# uCschematic.net
KiCad netlist of a schematic drawn in EAGLE
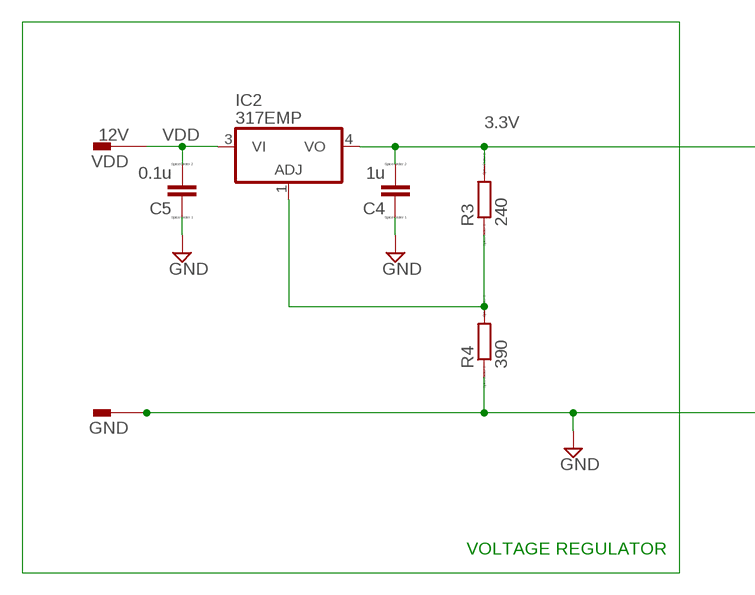
[diagram p0: schematic, sheet 1, part 1 of 2]
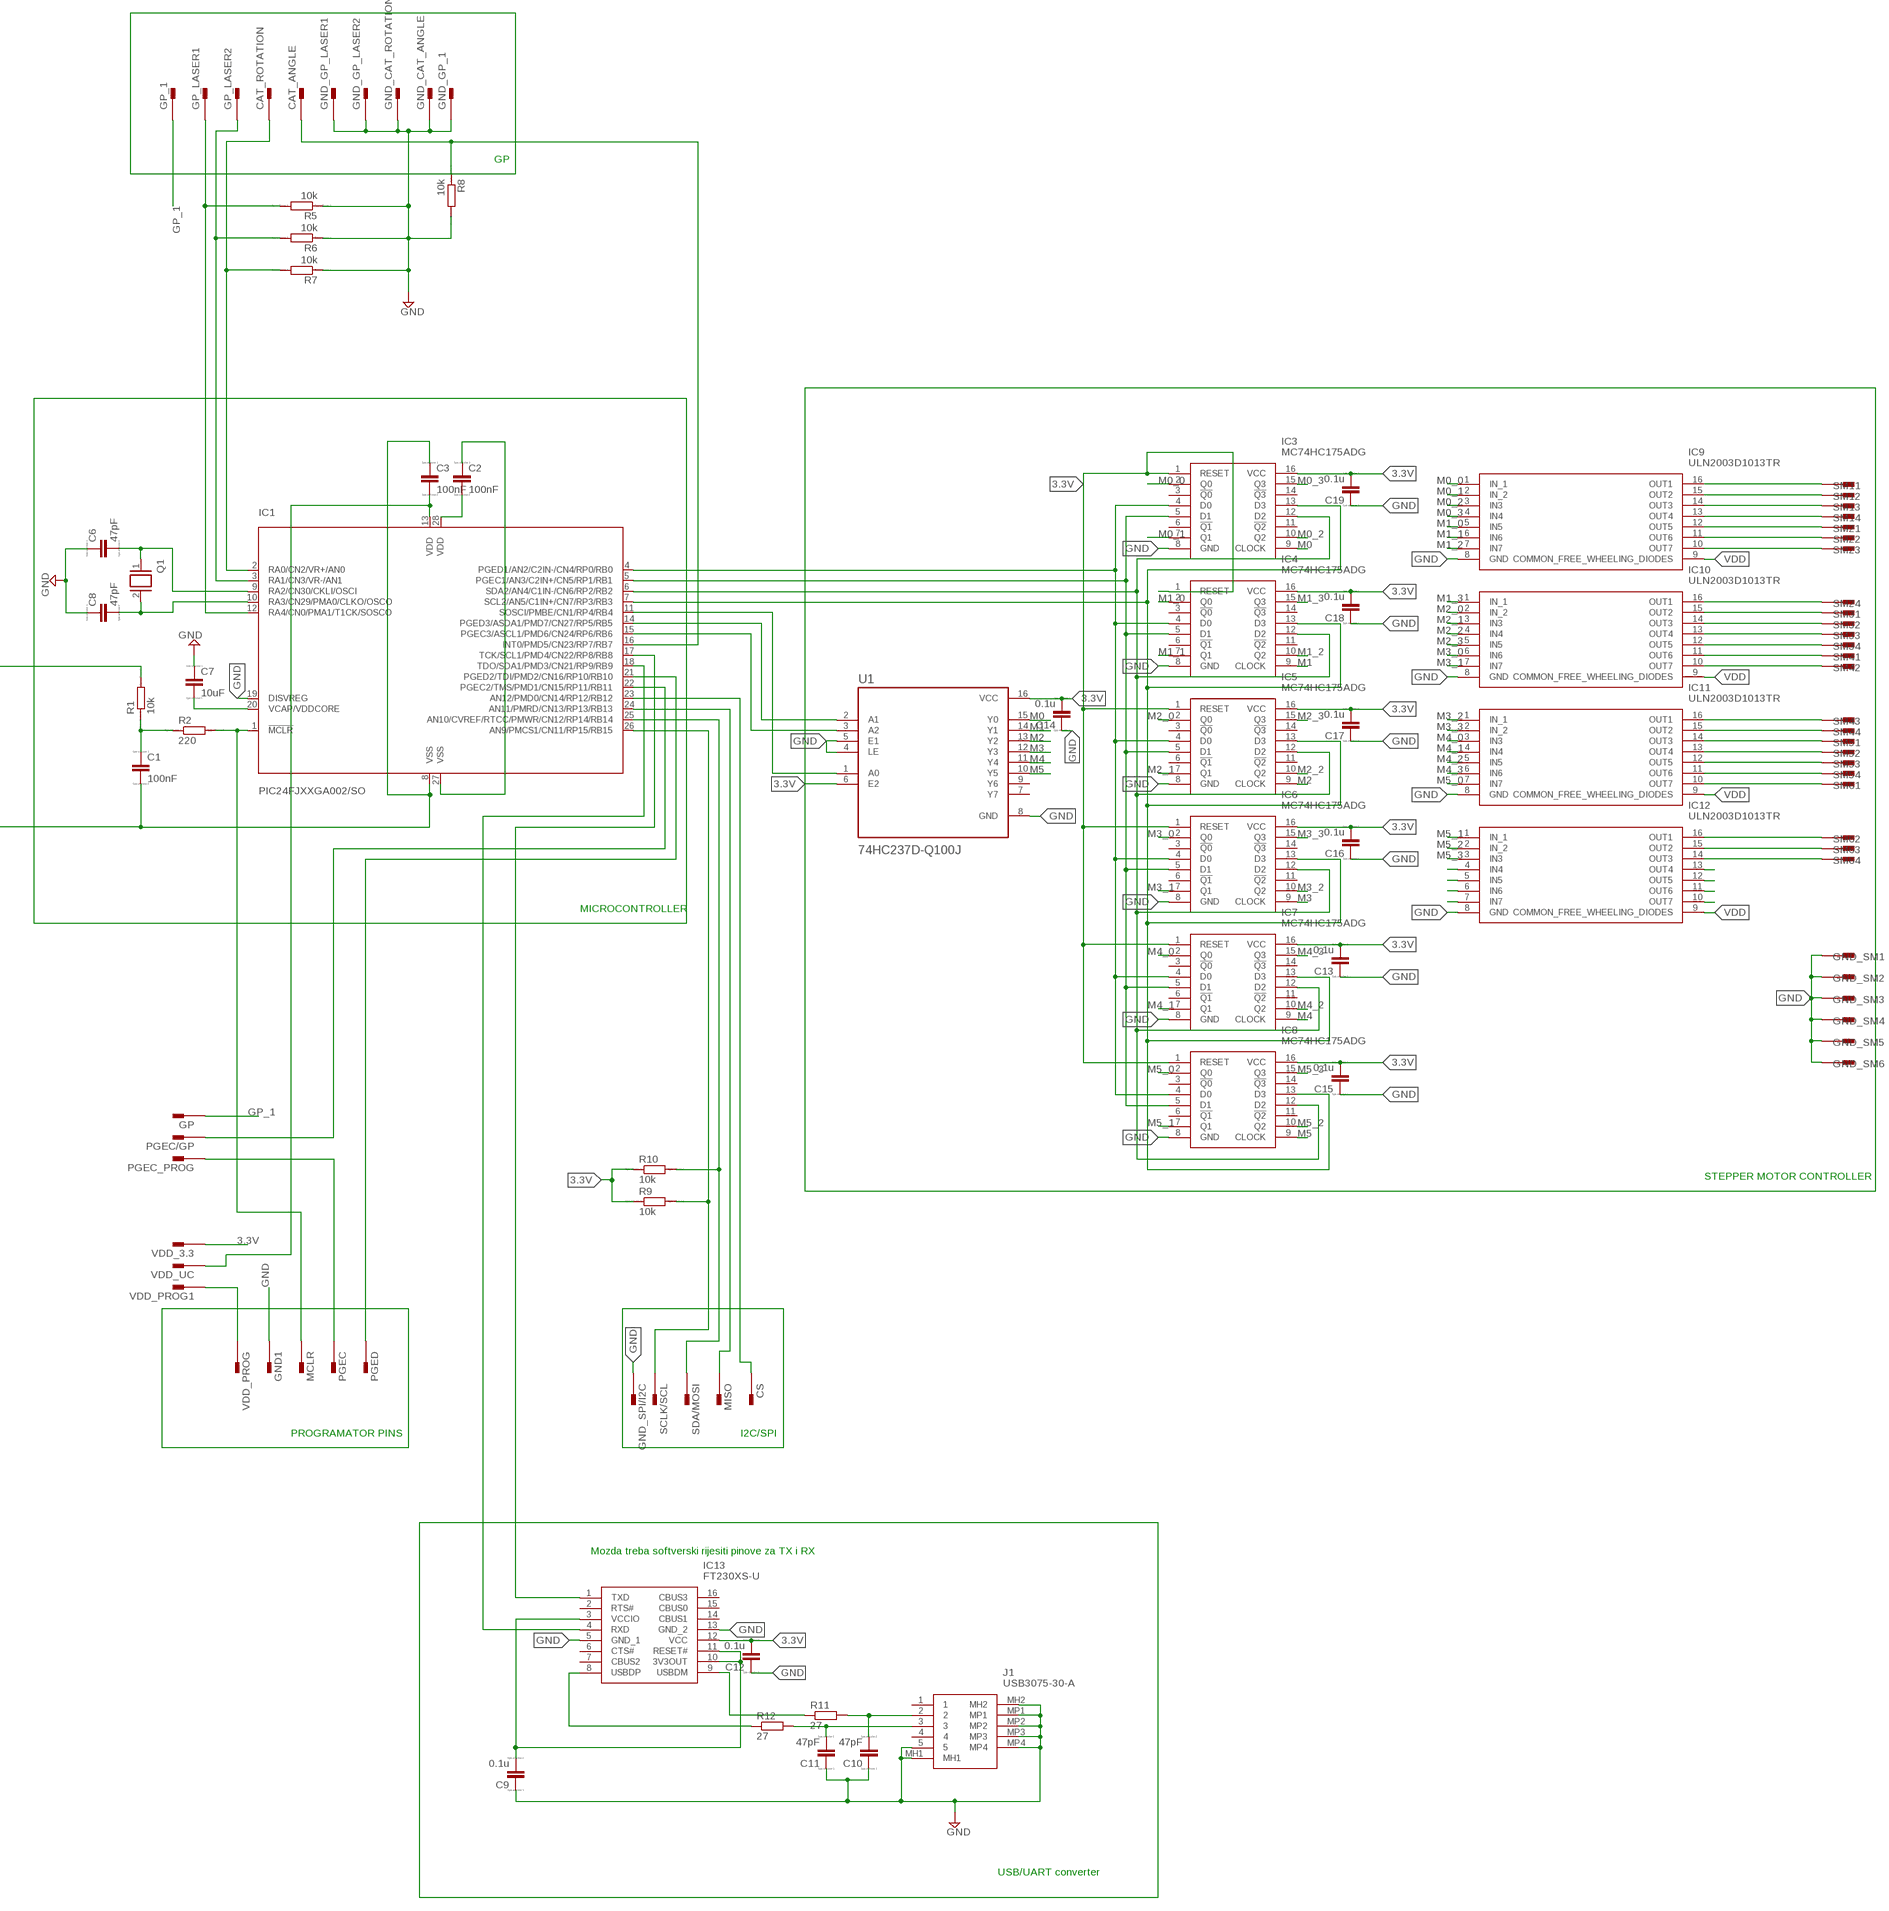
[diagram p1: schematic, sheet 1, part 2 of 2]

(export (version "E")
  (design (tool "Eeschema 10.0.6"))
  (components
    (comp (ref "C1")
      (value "100nF")
      (footprint "eagle-import:C0805")
      (libsource (lib "eagle-import") (part "C"))
    )
    (comp (ref "C2")
      (value "100nF")
      (footprint "eagle-import:C0805")
      (libsource (lib "eagle-import") (part "C"))
    )
    (comp (ref "C3")
      (value "100nF")
      (footprint "eagle-import:C0805")
      (libsource (lib "eagle-import") (part "C"))
    )
    (comp (ref "C4")
      (value "1u")
      (footprint "eagle-import:C0805")
      (libsource (lib "eagle-import") (part "C"))
    )
    (comp (ref "C5")
      (value "0.1u")
      (footprint "eagle-import:C0805")
      (libsource (lib "eagle-import") (part "C"))
    )
    (comp (ref "C6")
      (value "47pF")
      (footprint "eagle-import:C0805")
      (libsource (lib "eagle-import") (part "C"))
    )
    (comp (ref "C7")
      (value "10uF")
      (footprint "eagle-import:C0805")
      (libsource (lib "eagle-import") (part "C"))
    )
    (comp (ref "C8")
      (value "47pF")
      (footprint "eagle-import:C0805")
      (libsource (lib "eagle-import") (part "C"))
    )
    (comp (ref "C9")
      (value "0.1u")
      (footprint "eagle-import:C0805")
      (libsource (lib "eagle-import") (part "C"))
    )
    (comp (ref "C10")
      (value "47pF")
      (footprint "eagle-import:C0805")
      (libsource (lib "eagle-import") (part "C"))
    )
    (comp (ref "C11")
      (value "47pF")
      (footprint "eagle-import:C0805")
      (libsource (lib "eagle-import") (part "C"))
    )
    (comp (ref "C12")
      (value "0.1u")
      (footprint "eagle-import:C0805")
      (libsource (lib "eagle-import") (part "C"))
    )
    (comp (ref "C13")
      (value "0.1u")
      (footprint "eagle-import:C0805")
      (libsource (lib "eagle-import") (part "C"))
    )
    (comp (ref "C14")
      (value "0.1u")
      (footprint "eagle-import:C0805")
      (libsource (lib "eagle-import") (part "C"))
    )
    (comp (ref "C15")
      (value "0.1u")
      (footprint "eagle-import:C0805")
      (libsource (lib "eagle-import") (part "C"))
    )
    (comp (ref "C16")
      (value "0.1u")
      (footprint "eagle-import:C0805")
      (libsource (lib "eagle-import") (part "C"))
    )
    (comp (ref "C17")
      (value "0.1u")
      (footprint "eagle-import:C0805")
      (libsource (lib "eagle-import") (part "C"))
    )
    (comp (ref "C18")
      (value "0.1u")
      (footprint "eagle-import:C0805")
      (libsource (lib "eagle-import") (part "C"))
    )
    (comp (ref "C19")
      (value "0.1u")
      (footprint "eagle-import:C0805")
      (libsource (lib "eagle-import") (part "C"))
    )
    (comp (ref "CAT_ANGLE")
      (value "PIN1-2")
      (footprint "eagle-import:62221")
      (fields (field (name "MF") "TYCO ELECTRONICS") (field (name "MPN") "62221-1"))
      (libsource (lib "eagle-import") (part "PIN1-2"))
    )
    (comp (ref "CAT_ROTATION")
      (value "PIN1-2")
      (footprint "eagle-import:62221")
      (fields (field (name "MF") "TYCO ELECTRONICS") (field (name "MPN") "62221-1"))
      (libsource (lib "eagle-import") (part "PIN1-2"))
    )
    (comp (ref "CS")
      (value "PIN1-2")
      (footprint "eagle-import:62221")
      (fields (field (name "MF") "TYCO ELECTRONICS") (field (name "MPN") "62221-1"))
      (libsource (lib "eagle-import") (part "PIN1-2"))
    )
    (comp (ref "GND")
      (value "PIN1-2")
      (footprint "eagle-import:62221")
      (fields (field (name "MF") "TYCO ELECTRONICS") (field (name "MPN") "62221-1"))
      (libsource (lib "eagle-import") (part "PIN1-2"))
    )
    (comp (ref "GND1")
      (value "PIN1-2")
      (footprint "eagle-import:62221")
      (fields (field (name "MF") "TYCO ELECTRONICS") (field (name "MPN") "62221-1"))
      (libsource (lib "eagle-import") (part "PIN1-2"))
    )
    (comp (ref "GND_CAT_ANGLE")
      (value "PIN1-2")
      (footprint "eagle-import:62221")
      (fields (field (name "MF") "TYCO ELECTRONICS") (field (name "MPN") "62221-1"))
      (libsource (lib "eagle-import") (part "PIN1-2"))
    )
    (comp (ref "GND_CAT_ROTATION")
      (value "PIN1-2")
      (footprint "eagle-import:62221")
      (fields (field (name "MF") "TYCO ELECTRONICS") (field (name "MPN") "62221-1"))
      (libsource (lib "eagle-import") (part "PIN1-2"))
    )
    (comp (ref "GND_GP_1")
      (value "PIN1-2")
      (footprint "eagle-import:62221")
      (fields (field (name "MF") "TYCO ELECTRONICS") (field (name "MPN") "62221-1"))
      (libsource (lib "eagle-import") (part "PIN1-2"))
    )
    (comp (ref "GND_GP_LASER1")
      (value "PIN1-2")
      (footprint "eagle-import:62221")
      (fields (field (name "MF") "TYCO ELECTRONICS") (field (name "MPN") "62221-1"))
      (libsource (lib "eagle-import") (part "PIN1-2"))
    )
    (comp (ref "GND_GP_LASER2")
      (value "PIN1-2")
      (footprint "eagle-import:62221")
      (fields (field (name "MF") "TYCO ELECTRONICS") (field (name "MPN") "62221-1"))
      (libsource (lib "eagle-import") (part "PIN1-2"))
    )
    (comp (ref "GND_SM1")
      (value "PIN1-2")
      (footprint "eagle-import:62221")
      (fields (field (name "MF") "TYCO ELECTRONICS") (field (name "MPN") "62221-1"))
      (libsource (lib "eagle-import") (part "PIN1-2"))
    )
    (comp (ref "GND_SM2")
      (value "PIN1-2")
      (footprint "eagle-import:62221")
      (fields (field (name "MF") "TYCO ELECTRONICS") (field (name "MPN") "62221-1"))
      (libsource (lib "eagle-import") (part "PIN1-2"))
    )
    (comp (ref "GND_SM3")
      (value "PIN1-2")
      (footprint "eagle-import:62221")
      (fields (field (name "MF") "TYCO ELECTRONICS") (field (name "MPN") "62221-1"))
      (libsource (lib "eagle-import") (part "PIN1-2"))
    )
    (comp (ref "GND_SM4")
      (value "PIN1-2")
      (footprint "eagle-import:62221")
      (fields (field (name "MF") "TYCO ELECTRONICS") (field (name "MPN") "62221-1"))
      (libsource (lib "eagle-import") (part "PIN1-2"))
    )
    (comp (ref "GND_SM5")
      (value "PIN1-2")
      (footprint "eagle-import:62221")
      (fields (field (name "MF") "TYCO ELECTRONICS") (field (name "MPN") "62221-1"))
      (libsource (lib "eagle-import") (part "PIN1-2"))
    )
    (comp (ref "GND_SM6")
      (value "PIN1-2")
      (footprint "eagle-import:62221")
      (fields (field (name "MF") "TYCO ELECTRONICS") (field (name "MPN") "62221-1"))
      (libsource (lib "eagle-import") (part "PIN1-2"))
    )
    (comp (ref "GND_SPI/I2C")
      (value "PIN1-2")
      (footprint "eagle-import:62221")
      (fields (field (name "MF") "TYCO ELECTRONICS") (field (name "MPN") "62221-1"))
      (libsource (lib "eagle-import") (part "PIN1-2"))
    )
    (comp (ref "GP")
      (value "PIN1-2")
      (footprint "eagle-import:62221")
      (fields (field (name "MF") "TYCO ELECTRONICS") (field (name "MPN") "62221-1"))
      (libsource (lib "eagle-import") (part "PIN1-2"))
    )
    (comp (ref "GP_1")
      (value "PIN1-2")
      (footprint "eagle-import:62221")
      (fields (field (name "MF") "TYCO ELECTRONICS") (field (name "MPN") "62221-1"))
      (libsource (lib "eagle-import") (part "PIN1-2"))
    )
    (comp (ref "GP_LASER1")
      (value "PIN1-2")
      (footprint "eagle-import:62221")
      (fields (field (name "MF") "TYCO ELECTRONICS") (field (name "MPN") "62221-1"))
      (libsource (lib "eagle-import") (part "PIN1-2"))
    )
    (comp (ref "GP_LASER2")
      (value "PIN1-2")
      (footprint "eagle-import:62221")
      (fields (field (name "MF") "TYCO ELECTRONICS") (field (name "MPN") "62221-1"))
      (libsource (lib "eagle-import") (part "PIN1-2"))
    )
    (comp (ref "IC1")
      (value "PIC24FJXXGA002/SO")
      (footprint "eagle-import:SO28W")
      (libsource (lib "eagle-import") (part "PIC24FJXXGA002/SO"))
    )
    (comp (ref "IC2")
      (value "317EMP")
      (footprint "eagle-import:SOT223")
      (libsource (lib "eagle-import") (part "317EMP"))
    )
    (comp (ref "IC3")
      (value "MC74HC175ADG")
      (footprint "eagle-import:SOIC127P600X175-16N")
      (fields (field (name "MOUSER_PART_NUMBER") "863-MC74HC175ADG"))
      (libsource (lib "eagle-import") (part "MC74HC175ADG"))
    )
    (comp (ref "IC4")
      (value "MC74HC175ADG")
      (footprint "eagle-import:SOIC127P600X175-16N")
      (fields (field (name "MOUSER_PART_NUMBER") "863-MC74HC175ADG"))
      (libsource (lib "eagle-import") (part "MC74HC175ADG"))
    )
    (comp (ref "IC5")
      (value "MC74HC175ADG")
      (footprint "eagle-import:SOIC127P600X175-16N")
      (fields (field (name "MOUSER_PART_NUMBER") "863-MC74HC175ADG"))
      (libsource (lib "eagle-import") (part "MC74HC175ADG"))
    )
    (comp (ref "IC6")
      (value "MC74HC175ADG")
      (footprint "eagle-import:SOIC127P600X175-16N")
      (fields (field (name "MOUSER_PART_NUMBER") "863-MC74HC175ADG"))
      (libsource (lib "eagle-import") (part "MC74HC175ADG"))
    )
    (comp (ref "IC7")
      (value "MC74HC175ADG")
      (footprint "eagle-import:SOIC127P600X175-16N")
      (fields (field (name "MOUSER_PART_NUMBER") "863-MC74HC175ADG"))
      (libsource (lib "eagle-import") (part "MC74HC175ADG"))
    )
    (comp (ref "IC8")
      (value "MC74HC175ADG")
      (footprint "eagle-import:SOIC127P600X175-16N")
      (fields (field (name "MOUSER_PART_NUMBER") "863-MC74HC175ADG"))
      (libsource (lib "eagle-import") (part "MC74HC175ADG"))
    )
    (comp (ref "IC9")
      (value "ULN2003D1013TR")
      (footprint "eagle-import:SOIC127P600X175-16N")
      (fields (field (name "MOUSER_PART_NUMBER") "511-ULN2003D1013TR"))
      (libsource (lib "eagle-import") (part "ULN2003D1013TR"))
    )
    (comp (ref "IC10")
      (value "ULN2003D1013TR")
      (footprint "eagle-import:SOIC127P600X175-16N")
      (fields (field (name "MOUSER_PART_NUMBER") "511-ULN2003D1013TR"))
      (libsource (lib "eagle-import") (part "ULN2003D1013TR"))
    )
    (comp (ref "IC11")
      (value "ULN2003D1013TR")
      (footprint "eagle-import:SOIC127P600X175-16N")
      (fields (field (name "MOUSER_PART_NUMBER") "511-ULN2003D1013TR"))
      (libsource (lib "eagle-import") (part "ULN2003D1013TR"))
    )
    (comp (ref "IC12")
      (value "ULN2003D1013TR")
      (footprint "eagle-import:SOIC127P600X175-16N")
      (fields (field (name "MOUSER_PART_NUMBER") "511-ULN2003D1013TR"))
      (libsource (lib "eagle-import") (part "ULN2003D1013TR"))
    )
    (comp (ref "IC13")
      (value "FT230XS-U")
      (footprint "eagle-import:SOP64P599X175-16N")
      (fields (field (name "MOUSER_PART_NUMBER") "895-FT230XS-U"))
      (libsource (lib "eagle-import") (part "FT230XS-U"))
    )
    (comp (ref "J1")
      (value "USB3075-30-A")
      (footprint "eagle-import:USB307530A")
      (fields (field (name "MOUSER_PART_NUMBER") "640-USB3075-30-A"))
      (libsource (lib "eagle-import") (part "USB3075-30-A"))
    )
    (comp (ref "MCLR")
      (value "PIN1-2")
      (footprint "eagle-import:62221")
      (fields (field (name "MF") "TYCO ELECTRONICS") (field (name "MPN") "62221-1"))
      (libsource (lib "eagle-import") (part "PIN1-2"))
    )
    (comp (ref "MISO")
      (value "PIN1-2")
      (footprint "eagle-import:62221")
      (fields (field (name "MF") "TYCO ELECTRONICS") (field (name "MPN") "62221-1"))
      (libsource (lib "eagle-import") (part "PIN1-2"))
    )
    (comp (ref "PGEC")
      (value "PIN1-2")
      (footprint "eagle-import:62221")
      (fields (field (name "MF") "TYCO ELECTRONICS") (field (name "MPN") "62221-1"))
      (libsource (lib "eagle-import") (part "PIN1-2"))
    )
    (comp (ref "PGEC/GP")
      (value "PIN1-2")
      (footprint "eagle-import:62221")
      (fields (field (name "MF") "TYCO ELECTRONICS") (field (name "MPN") "62221-1"))
      (libsource (lib "eagle-import") (part "PIN1-2"))
    )
    (comp (ref "PGEC_PROG")
      (value "PIN1-2")
      (footprint "eagle-import:62221")
      (fields (field (name "MF") "TYCO ELECTRONICS") (field (name "MPN") "62221-1"))
      (libsource (lib "eagle-import") (part "PIN1-2"))
    )
    (comp (ref "PGED")
      (value "PIN1-2")
      (footprint "eagle-import:62221")
      (fields (field (name "MF") "TYCO ELECTRONICS") (field (name "MPN") "62221-1"))
      (libsource (lib "eagle-import") (part "PIN1-2"))
    )
    (comp (ref "Q1")
      (value "XTAL/S")
      (footprint "eagle-import:QS")
      (libsource (lib "eagle-import") (part "XTAL/S"))
    )
    (comp (ref "R1")
      (value "10k")
      (footprint "eagle-import:R0805")
      (libsource (lib "eagle-import") (part "R"))
    )
    (comp (ref "R2")
      (value "220")
      (footprint "eagle-import:R0805")
      (libsource (lib "eagle-import") (part "R"))
    )
    (comp (ref "R3")
      (value "240")
      (footprint "eagle-import:R0805")
      (libsource (lib "eagle-import") (part "R"))
    )
    (comp (ref "R4")
      (value "390")
      (footprint "eagle-import:R0805")
      (libsource (lib "eagle-import") (part "R"))
    )
    (comp (ref "R5")
      (value "10k")
      (footprint "eagle-import:R0805")
      (libsource (lib "eagle-import") (part "R"))
    )
    (comp (ref "R6")
      (value "10k")
      (footprint "eagle-import:R0805")
      (libsource (lib "eagle-import") (part "R"))
    )
    (comp (ref "R7")
      (value "10k")
      (footprint "eagle-import:R0805")
      (libsource (lib "eagle-import") (part "R"))
    )
    (comp (ref "R8")
      (value "10k")
      (footprint "eagle-import:R0805")
      (libsource (lib "eagle-import") (part "R"))
    )
    (comp (ref "R9")
      (value "10k")
      (footprint "eagle-import:R0805")
      (libsource (lib "eagle-import") (part "R"))
    )
    (comp (ref "R10")
      (value "10k")
      (footprint "eagle-import:R0805")
      (libsource (lib "eagle-import") (part "R"))
    )
    (comp (ref "R11")
      (value "27")
      (footprint "eagle-import:R0805")
      (libsource (lib "eagle-import") (part "R-EU_R0805"))
    )
    (comp (ref "R12")
      (value "27")
      (footprint "eagle-import:R0805")
      (libsource (lib "eagle-import") (part "R-EU_R0805"))
    )
    (comp (ref "SCLK/SCL")
      (value "PIN1-2")
      (footprint "eagle-import:62221")
      (fields (field (name "MF") "TYCO ELECTRONICS") (field (name "MPN") "62221-1"))
      (libsource (lib "eagle-import") (part "PIN1-2"))
    )
    (comp (ref "SDA/MOSI")
      (value "PIN1-2")
      (footprint "eagle-import:62221")
      (fields (field (name "MF") "TYCO ELECTRONICS") (field (name "MPN") "62221-1"))
      (libsource (lib "eagle-import") (part "PIN1-2"))
    )
    (comp (ref "SM11")
      (value "PIN1-2")
      (footprint "eagle-import:62221")
      (fields (field (name "MF") "TYCO ELECTRONICS") (field (name "MPN") "62221-1"))
      (libsource (lib "eagle-import") (part "PIN1-2"))
    )
    (comp (ref "SM12")
      (value "PIN1-2")
      (footprint "eagle-import:62221")
      (fields (field (name "MF") "TYCO ELECTRONICS") (field (name "MPN") "62221-1"))
      (libsource (lib "eagle-import") (part "PIN1-2"))
    )
    (comp (ref "SM13")
      (value "PIN1-2")
      (footprint "eagle-import:62221")
      (fields (field (name "MF") "TYCO ELECTRONICS") (field (name "MPN") "62221-1"))
      (libsource (lib "eagle-import") (part "PIN1-2"))
    )
    (comp (ref "SM14")
      (value "PIN1-2")
      (footprint "eagle-import:62221")
      (fields (field (name "MF") "TYCO ELECTRONICS") (field (name "MPN") "62221-1"))
      (libsource (lib "eagle-import") (part "PIN1-2"))
    )
    (comp (ref "SM21")
      (value "PIN1-2")
      (footprint "eagle-import:62221")
      (fields (field (name "MF") "TYCO ELECTRONICS") (field (name "MPN") "62221-1"))
      (libsource (lib "eagle-import") (part "PIN1-2"))
    )
    (comp (ref "SM22")
      (value "PIN1-2")
      (footprint "eagle-import:62221")
      (fields (field (name "MF") "TYCO ELECTRONICS") (field (name "MPN") "62221-1"))
      (libsource (lib "eagle-import") (part "PIN1-2"))
    )
    (comp (ref "SM23")
      (value "PIN1-2")
      (footprint "eagle-import:62221")
      (fields (field (name "MF") "TYCO ELECTRONICS") (field (name "MPN") "62221-1"))
      (libsource (lib "eagle-import") (part "PIN1-2"))
    )
    (comp (ref "SM24")
      (value "PIN1-2")
      (footprint "eagle-import:62221")
      (fields (field (name "MF") "TYCO ELECTRONICS") (field (name "MPN") "62221-1"))
      (libsource (lib "eagle-import") (part "PIN1-2"))
    )
    (comp (ref "SM31")
      (value "PIN1-2")
      (footprint "eagle-import:62221")
      (fields (field (name "MF") "TYCO ELECTRONICS") (field (name "MPN") "62221-1"))
      (libsource (lib "eagle-import") (part "PIN1-2"))
    )
    (comp (ref "SM32")
      (value "PIN1-2")
      (footprint "eagle-import:62221")
      (fields (field (name "MF") "TYCO ELECTRONICS") (field (name "MPN") "62221-1"))
      (libsource (lib "eagle-import") (part "PIN1-2"))
    )
    (comp (ref "SM33")
      (value "PIN1-2")
      (footprint "eagle-import:62221")
      (fields (field (name "MF") "TYCO ELECTRONICS") (field (name "MPN") "62221-1"))
      (libsource (lib "eagle-import") (part "PIN1-2"))
    )
    (comp (ref "SM34")
      (value "PIN1-2")
      (footprint "eagle-import:62221")
      (fields (field (name "MF") "TYCO ELECTRONICS") (field (name "MPN") "62221-1"))
      (libsource (lib "eagle-import") (part "PIN1-2"))
    )
    (comp (ref "SM41")
      (value "PIN1-2")
      (footprint "eagle-import:62221")
      (fields (field (name "MF") "TYCO ELECTRONICS") (field (name "MPN") "62221-1"))
      (libsource (lib "eagle-import") (part "PIN1-2"))
    )
    (comp (ref "SM42")
      (value "PIN1-2")
      (footprint "eagle-import:62221")
      (fields (field (name "MF") "TYCO ELECTRONICS") (field (name "MPN") "62221-1"))
      (libsource (lib "eagle-import") (part "PIN1-2"))
    )
    (comp (ref "SM43")
      (value "PIN1-2")
      (footprint "eagle-import:62221")
      (fields (field (name "MF") "TYCO ELECTRONICS") (field (name "MPN") "62221-1"))
      (libsource (lib "eagle-import") (part "PIN1-2"))
    )
    (comp (ref "SM44")
      (value "PIN1-2")
      (footprint "eagle-import:62221")
      (fields (field (name "MF") "TYCO ELECTRONICS") (field (name "MPN") "62221-1"))
      (libsource (lib "eagle-import") (part "PIN1-2"))
    )
    (comp (ref "SM51")
      (value "PIN1-2")
      (footprint "eagle-import:62221")
      (fields (field (name "MF") "TYCO ELECTRONICS") (field (name "MPN") "62221-1"))
      (libsource (lib "eagle-import") (part "PIN1-2"))
    )
    (comp (ref "SM52")
      (value "PIN1-2")
      (footprint "eagle-import:62221")
      (fields (field (name "MF") "TYCO ELECTRONICS") (field (name "MPN") "62221-1"))
      (libsource (lib "eagle-import") (part "PIN1-2"))
    )
    (comp (ref "SM53")
      (value "PIN1-2")
      (footprint "eagle-import:62221")
      (fields (field (name "MF") "TYCO ELECTRONICS") (field (name "MPN") "62221-1"))
      (libsource (lib "eagle-import") (part "PIN1-2"))
    )
    (comp (ref "SM54")
      (value "PIN1-2")
      (footprint "eagle-import:62221")
      (fields (field (name "MF") "TYCO ELECTRONICS") (field (name "MPN") "62221-1"))
      (libsource (lib "eagle-import") (part "PIN1-2"))
    )
    (comp (ref "SM61")
      (value "PIN1-2")
      (footprint "eagle-import:62221")
      (fields (field (name "MF") "TYCO ELECTRONICS") (field (name "MPN") "62221-1"))
      (libsource (lib "eagle-import") (part "PIN1-2"))
    )
    (comp (ref "SM62")
      (value "PIN1-2")
      (footprint "eagle-import:62221")
      (fields (field (name "MF") "TYCO ELECTRONICS") (field (name "MPN") "62221-1"))
      (libsource (lib "eagle-import") (part "PIN1-2"))
    )
    (comp (ref "SM63")
      (value "PIN1-2")
      (footprint "eagle-import:62221")
      (fields (field (name "MF") "TYCO ELECTRONICS") (field (name "MPN") "62221-1"))
      (libsource (lib "eagle-import") (part "PIN1-2"))
    )
    (comp (ref "SM64")
      (value "PIN1-2")
      (footprint "eagle-import:62221")
      (fields (field (name "MF") "TYCO ELECTRONICS") (field (name "MPN") "62221-1"))
      (libsource (lib "eagle-import") (part "PIN1-2"))
    )
    (comp (ref "U1")
      (value "74HC237D-Q100J")
      (footprint "eagle-import:SOIC127P600X175-16N")
      (fields (field (name "MF") "Nexperia USA Inc."))
      (libsource (lib "eagle-import") (part "74HC237D-Q100J"))
    )
    (comp (ref "VDD")
      (value "12V")
      (footprint "eagle-import:62221")
      (fields (field (name "MF") "TYCO ELECTRONICS") (field (name "MPN") "62221-1"))
      (libsource (lib "eagle-import") (part "PIN1-2"))
    )
    (comp (ref "VDD_3.3")
      (value "PIN1-2")
      (footprint "eagle-import:62221")
      (fields (field (name "MF") "TYCO ELECTRONICS") (field (name "MPN") "62221-1"))
      (libsource (lib "eagle-import") (part "PIN1-2"))
    )
    (comp (ref "VDD_PROG")
      (value "PIN1-2")
      (footprint "eagle-import:62221")
      (fields (field (name "MF") "TYCO ELECTRONICS") (field (name "MPN") "62221-1"))
      (libsource (lib "eagle-import") (part "PIN1-2"))
    )
    (comp (ref "VDD_PROG1")
      (value "PIN1-2")
      (footprint "eagle-import:62221")
      (fields (field (name "MF") "TYCO ELECTRONICS") (field (name "MPN") "62221-1"))
      (libsource (lib "eagle-import") (part "PIN1-2"))
    )
    (comp (ref "VDD_UC")
      (value "PIN1-2")
      (footprint "eagle-import:62221")
      (fields (field (name "MF") "TYCO ELECTRONICS") (field (name "MPN") "62221-1"))
      (libsource (lib "eagle-import") (part "PIN1-2"))
    )
  )
  (nets
    (net (code "1") (name "/GP_1") (class "Default")
      (node (ref "GP") (pin "1") (pinfunction "1_1") (pintype "passive"))
      (node (ref "GP_1") (pin "1") (pinfunction "1_1") (pintype "passive"))
    )
    (net (code "2") (name "/M0") (class "Default")
      (node (ref "IC3") (pin "9") (pinfunction "CLOCK_9") (pintype "bidirectional"))
      (node (ref "U1") (pin "15") (pinfunction "Y0_15") (pintype "output"))
    )
    (net (code "3") (name "/M0_0") (class "Default")
      (node (ref "IC3") (pin "2") (pinfunction "Q0_2") (pintype "bidirectional"))
      (node (ref "IC9") (pin "1") (pinfunction "IN_1_1") (pintype "bidirectional"))
    )
    (net (code "4") (name "/M0_1") (class "Default")
      (node (ref "IC3") (pin "7") (pinfunction "Q1_7") (pintype "bidirectional"))
      (node (ref "IC9") (pin "2") (pinfunction "IN_2_2") (pintype "bidirectional"))
    )
    (net (code "5") (name "/M0_2") (class "Default")
      (node (ref "IC3") (pin "10") (pinfunction "Q2_10") (pintype "bidirectional"))
      (node (ref "IC9") (pin "3") (pinfunction "IN3_3") (pintype "bidirectional"))
    )
    (net (code "6") (name "/M0_3") (class "Default")
      (node (ref "IC3") (pin "15") (pinfunction "Q3_15") (pintype "bidirectional"))
      (node (ref "IC9") (pin "4") (pinfunction "IN4_4") (pintype "bidirectional"))
    )
    (net (code "7") (name "/M1") (class "Default")
      (node (ref "IC4") (pin "9") (pinfunction "CLOCK_9") (pintype "bidirectional"))
      (node (ref "U1") (pin "14") (pinfunction "Y1_14") (pintype "output"))
    )
    (net (code "8") (name "/M1_0") (class "Default")
      (node (ref "IC4") (pin "2") (pinfunction "Q0_2") (pintype "bidirectional"))
      (node (ref "IC9") (pin "5") (pinfunction "IN5_5") (pintype "bidirectional"))
    )
    (net (code "9") (name "/M1_1") (class "Default")
      (node (ref "IC4") (pin "7") (pinfunction "Q1_7") (pintype "bidirectional"))
      (node (ref "IC9") (pin "6") (pinfunction "IN6_6") (pintype "bidirectional"))
    )
    (net (code "10") (name "/M1_2") (class "Default")
      (node (ref "IC4") (pin "10") (pinfunction "Q2_10") (pintype "bidirectional"))
      (node (ref "IC9") (pin "7") (pinfunction "IN7_7") (pintype "bidirectional"))
    )
    (net (code "11") (name "/M1_3") (class "Default")
      (node (ref "IC10") (pin "1") (pinfunction "IN_1_1") (pintype "bidirectional"))
      (node (ref "IC4") (pin "15") (pinfunction "Q3_15") (pintype "bidirectional"))
    )
    (net (code "12") (name "/M2") (class "Default")
      (node (ref "IC5") (pin "9") (pinfunction "CLOCK_9") (pintype "bidirectional"))
      (node (ref "U1") (pin "13") (pinfunction "Y2_13") (pintype "output"))
    )
    (net (code "13") (name "/M2_0") (class "Default")
      (node (ref "IC10") (pin "2") (pinfunction "IN_2_2") (pintype "bidirectional"))
      (node (ref "IC5") (pin "2") (pinfunction "Q0_2") (pintype "bidirectional"))
    )
    (net (code "14") (name "/M2_1") (class "Default")
      (node (ref "IC10") (pin "3") (pinfunction "IN3_3") (pintype "bidirectional"))
      (node (ref "IC5") (pin "7") (pinfunction "Q1_7") (pintype "bidirectional"))
    )
    (net (code "15") (name "/M2_2") (class "Default")
      (node (ref "IC10") (pin "4") (pinfunction "IN4_4") (pintype "bidirectional"))
      (node (ref "IC5") (pin "10") (pinfunction "Q2_10") (pintype "bidirectional"))
    )
    (net (code "16") (name "/M2_3") (class "Default")
      (node (ref "IC10") (pin "5") (pinfunction "IN5_5") (pintype "bidirectional"))
      (node (ref "IC5") (pin "15") (pinfunction "Q3_15") (pintype "bidirectional"))
    )
    (net (code "17") (name "/M3") (class "Default")
      (node (ref "IC6") (pin "9") (pinfunction "CLOCK_9") (pintype "bidirectional"))
      (node (ref "U1") (pin "12") (pinfunction "Y3_12") (pintype "output"))
    )
    (net (code "18") (name "/M3_0") (class "Default")
      (node (ref "IC10") (pin "6") (pinfunction "IN6_6") (pintype "bidirectional"))
      (node (ref "IC6") (pin "2") (pinfunction "Q0_2") (pintype "bidirectional"))
    )
    (net (code "19") (name "/M3_1") (class "Default")
      (node (ref "IC10") (pin "7") (pinfunction "IN7_7") (pintype "bidirectional"))
      (node (ref "IC6") (pin "7") (pinfunction "Q1_7") (pintype "bidirectional"))
    )
    (net (code "20") (name "/M3_2") (class "Default")
      (node (ref "IC11") (pin "1") (pinfunction "IN_1_1") (pintype "bidirectional"))
      (node (ref "IC6") (pin "10") (pinfunction "Q2_10") (pintype "bidirectional"))
    )
    (net (code "21") (name "/M3_3") (class "Default")
      (node (ref "IC11") (pin "2") (pinfunction "IN_2_2") (pintype "bidirectional"))
      (node (ref "IC6") (pin "15") (pinfunction "Q3_15") (pintype "bidirectional"))
    )
    (net (code "22") (name "/M4") (class "Default")
      (node (ref "IC7") (pin "9") (pinfunction "CLOCK_9") (pintype "bidirectional"))
      (node (ref "U1") (pin "11") (pinfunction "Y4_11") (pintype "output"))
    )
    (net (code "23") (name "/M4_0") (class "Default")
      (node (ref "IC11") (pin "3") (pinfunction "IN3_3") (pintype "bidirectional"))
      (node (ref "IC7") (pin "2") (pinfunction "Q0_2") (pintype "bidirectional"))
    )
    (net (code "24") (name "/M4_1") (class "Default")
      (node (ref "IC11") (pin "4") (pinfunction "IN4_4") (pintype "bidirectional"))
      (node (ref "IC7") (pin "7") (pinfunction "Q1_7") (pintype "bidirectional"))
    )
    (net (code "25") (name "/M4_2") (class "Default")
      (node (ref "IC11") (pin "5") (pinfunction "IN5_5") (pintype "bidirectional"))
      (node (ref "IC7") (pin "10") (pinfunction "Q2_10") (pintype "bidirectional"))
    )
    (net (code "26") (name "/M4_3") (class "Default")
      (node (ref "IC11") (pin "6") (pinfunction "IN6_6") (pintype "bidirectional"))
      (node (ref "IC7") (pin "15") (pinfunction "Q3_15") (pintype "bidirectional"))
    )
    (net (code "27") (name "/M5") (class "Default")
      (node (ref "IC8") (pin "9") (pinfunction "CLOCK_9") (pintype "bidirectional"))
      (node (ref "U1") (pin "10") (pinfunction "Y5_10") (pintype "output"))
    )
    (net (code "28") (name "/M5_0") (class "Default")
      (node (ref "IC11") (pin "7") (pinfunction "IN7_7") (pintype "bidirectional"))
      (node (ref "IC8") (pin "2") (pinfunction "Q0_2") (pintype "bidirectional"))
    )
    (net (code "29") (name "/M5_1") (class "Default")
      (node (ref "IC12") (pin "1") (pinfunction "IN_1_1") (pintype "bidirectional"))
      (node (ref "IC8") (pin "7") (pinfunction "Q1_7") (pintype "bidirectional"))
    )
    (net (code "30") (name "/M5_2") (class "Default")
      (node (ref "IC12") (pin "2") (pinfunction "IN_2_2") (pintype "bidirectional"))
      (node (ref "IC8") (pin "10") (pinfunction "Q2_10") (pintype "bidirectional"))
    )
    (net (code "31") (name "/M5_3") (class "Default")
      (node (ref "IC12") (pin "3") (pinfunction "IN3_3") (pintype "bidirectional"))
      (node (ref "IC8") (pin "15") (pinfunction "Q3_15") (pintype "bidirectional"))
    )
    (net (code "32") (name "3.3V") (class "Default")
      (node (ref "C12") (pin "2") (pinfunction "2_2") (pintype "passive"))
      (node (ref "C13") (pin "2") (pinfunction "2_2") (pintype "passive"))
      (node (ref "C14") (pin "2") (pinfunction "2_2") (pintype "passive"))
      (node (ref "C15") (pin "2") (pinfunction "2_2") (pintype "passive"))
      (node (ref "C16") (pin "2") (pinfunction "2_2") (pintype "passive"))
      (node (ref "C17") (pin "2") (pinfunction "2_2") (pintype "passive"))
      (node (ref "C18") (pin "2") (pinfunction "2_2") (pintype "passive"))
      (node (ref "C19") (pin "2") (pinfunction "2_2") (pintype "passive"))
      (node (ref "C4") (pin "2") (pinfunction "2_2") (pintype "passive"))
      (node (ref "IC13") (pin "12") (pinfunction "VCC_12") (pintype "bidirectional"))
      (node (ref "IC2") (pin "4") (pinfunction "VO_4") (pintype "passive"))
      (node (ref "IC3") (pin "1") (pinfunction "RESET_1") (pintype "bidirectional"))
      (node (ref "IC3") (pin "16") (pinfunction "VCC_16") (pintype "bidirectional"))
      (node (ref "IC4") (pin "1") (pinfunction "RESET_1") (pintype "bidirectional"))
      (node (ref "IC4") (pin "16") (pinfunction "VCC_16") (pintype "bidirectional"))
      (node (ref "IC5") (pin "1") (pinfunction "RESET_1") (pintype "bidirectional"))
      (node (ref "IC5") (pin "16") (pinfunction "VCC_16") (pintype "bidirectional"))
      (node (ref "IC6") (pin "1") (pinfunction "RESET_1") (pintype "bidirectional"))
      (node (ref "IC6") (pin "16") (pinfunction "VCC_16") (pintype "bidirectional"))
      (node (ref "IC7") (pin "1") (pinfunction "RESET_1") (pintype "bidirectional"))
      (node (ref "IC7") (pin "16") (pinfunction "VCC_16") (pintype "bidirectional"))
      (node (ref "IC8") (pin "1") (pinfunction "RESET_1") (pintype "bidirectional"))
      (node (ref "IC8") (pin "16") (pinfunction "VCC_16") (pintype "bidirectional"))
      (node (ref "R1") (pin "2") (pinfunction "2_2") (pintype "passive"))
      (node (ref "R10") (pin "1") (pinfunction "1_1") (pintype "passive"))
      (node (ref "R3") (pin "2") (pinfunction "2_2") (pintype "passive"))
      (node (ref "R9") (pin "1") (pinfunction "1_1") (pintype "passive"))
      (node (ref "U1") (pin "16") (pinfunction "VCC_16") (pintype "power_in"))
      (node (ref "U1") (pin "6") (pinfunction "E2_6") (pintype "input"))
      (node (ref "VDD_3.3") (pin "1") (pinfunction "1_1") (pintype "passive"))
    )
    (net (code "33") (name "GND") (class "Default")
      (node (ref "C1") (pin "2") (pinfunction "2_2") (pintype "passive"))
      (node (ref "C10") (pin "1") (pinfunction "1_1") (pintype "passive"))
      (node (ref "C11") (pin "1") (pinfunction "1_1") (pintype "passive"))
      (node (ref "C12") (pin "1") (pinfunction "1_1") (pintype "passive"))
      (node (ref "C14") (pin "1") (pinfunction "1_1") (pintype "passive"))
      (node (ref "C3") (pin "1") (pinfunction "1_1") (pintype "passive"))
      (node (ref "C4") (pin "1") (pinfunction "1_1") (pintype "passive"))
      (node (ref "C5") (pin "1") (pinfunction "1_1") (pintype "passive"))
      (node (ref "C6") (pin "1") (pinfunction "1_1") (pintype "passive"))
      (node (ref "C7") (pin "1") (pinfunction "1_1") (pintype "passive"))
      (node (ref "C8") (pin "1") (pinfunction "1_1") (pintype "passive"))
      (node (ref "C9") (pin "1") (pinfunction "1_1") (pintype "passive"))
      (node (ref "GND") (pin "1") (pinfunction "1_1") (pintype "passive"))
      (node (ref "GND1") (pin "1") (pinfunction "1_1") (pintype "passive"))
      (node (ref "GND_CAT_ANGLE") (pin "1") (pinfunction "1_1") (pintype "passive"))
      (node (ref "GND_CAT_ROTATION") (pin "1") (pinfunction "1_1") (pintype "passive"))
      (node (ref "GND_GP_1") (pin "1") (pinfunction "1_1") (pintype "passive"))
      (node (ref "GND_GP_LASER1") (pin "1") (pinfunction "1_1") (pintype "passive"))
      (node (ref "GND_GP_LASER2") (pin "1") (pinfunction "1_1") (pintype "passive"))
      (node (ref "GND_SM1") (pin "1") (pinfunction "1_1") (pintype "passive"))
      (node (ref "GND_SM2") (pin "1") (pinfunction "1_1") (pintype "passive"))
      (node (ref "GND_SM3") (pin "1") (pinfunction "1_1") (pintype "passive"))
      (node (ref "GND_SM4") (pin "1") (pinfunction "1_1") (pintype "passive"))
      (node (ref "GND_SM5") (pin "1") (pinfunction "1_1") (pintype "passive"))
      (node (ref "GND_SM6") (pin "1") (pinfunction "1_1") (pintype "passive"))
      (node (ref "GND_SPI/I2C") (pin "1") (pinfunction "1_1") (pintype "passive"))
      (node (ref "IC1") (pin "19") (pinfunction "DISVREG_19") (pintype "input"))
      (node (ref "IC1") (pin "8") (pinfunction "VSS_8") (pintype "power_in"))
      (node (ref "IC10") (pin "8") (pinfunction "GND_8") (pintype "bidirectional"))
      (node (ref "IC11") (pin "8") (pinfunction "GND_8") (pintype "bidirectional"))
      (node (ref "IC12") (pin "8") (pinfunction "GND_8") (pintype "bidirectional"))
      (node (ref "IC13") (pin "13") (pinfunction "GND_2_13") (pintype "bidirectional"))
      (node (ref "IC13") (pin "5") (pinfunction "GND_1_5") (pintype "bidirectional"))
      (node (ref "IC3") (pin "8") (pinfunction "GND_8") (pintype "bidirectional"))
      (node (ref "IC4") (pin "8") (pinfunction "GND_8") (pintype "bidirectional"))
      (node (ref "IC5") (pin "8") (pinfunction "GND_8") (pintype "bidirectional"))
      (node (ref "IC6") (pin "8") (pinfunction "GND_8") (pintype "bidirectional"))
      (node (ref "IC7") (pin "8") (pinfunction "GND_8") (pintype "bidirectional"))
      (node (ref "IC8") (pin "8") (pinfunction "GND_8") (pintype "bidirectional"))
      (node (ref "IC9") (pin "8") (pinfunction "GND_8") (pintype "bidirectional"))
      (node (ref "J1") (pin "5") (pinfunction "5_5") (pintype "bidirectional"))
      (node (ref "J1") (pin "MH1") (pinfunction "MH1_MH1") (pintype "bidirectional"))
      (node (ref "J1") (pin "MH2") (pinfunction "MH2_MH2") (pintype "bidirectional"))
      (node (ref "J1") (pin "MP1") (pinfunction "MP1_MP1") (pintype "bidirectional"))
      (node (ref "J1") (pin "MP2") (pinfunction "MP2_MP2") (pintype "bidirectional"))
      (node (ref "J1") (pin "MP3") (pinfunction "MP3_MP3") (pintype "bidirectional"))
      (node (ref "J1") (pin "MP4") (pinfunction "MP4_MP4") (pintype "bidirectional"))
      (node (ref "R4") (pin "1") (pinfunction "1_1") (pintype "passive"))
      (node (ref "R5") (pin "1") (pinfunction "1_1") (pintype "passive"))
      (node (ref "R6") (pin "1") (pinfunction "1_1") (pintype "passive"))
      (node (ref "R7") (pin "1") (pinfunction "1_1") (pintype "passive"))
      (node (ref "R8") (pin "2") (pinfunction "2_2") (pintype "passive"))
      (node (ref "U1") (pin "4") (pinfunction "LE_4") (pintype "input"))
      (node (ref "U1") (pin "5") (pinfunction "E1_5") (pintype "input"))
      (node (ref "U1") (pin "8") (pinfunction "GND_8") (pintype "power_in"))
    )
    (net (code "34") (name "Net-(C1-Pad1)") (class "Default")
      (node (ref "C1") (pin "1") (pinfunction "1_1") (pintype "passive"))
      (node (ref "R1") (pin "1") (pinfunction "1_1") (pintype "passive"))
      (node (ref "R2") (pin "1") (pinfunction "1_1") (pintype "passive"))
    )
    (net (code "35") (name "Net-(C2-Pad1)") (class "Default")
      (node (ref "C2") (pin "1") (pinfunction "1_1") (pintype "passive"))
      (node (ref "IC1") (pin "27") (pinfunction "VSS_27") (pintype "power_in"))
    )
    (net (code "36") (name "Net-(C2-Pad2)") (class "Default")
      (node (ref "C2") (pin "2") (pinfunction "2_2") (pintype "passive"))
      (node (ref "IC1") (pin "28") (pinfunction "VDD_28") (pintype "power_in"))
    )
    (net (code "37") (name "Net-(C3-Pad2)") (class "Default")
      (node (ref "C3") (pin "2") (pinfunction "2_2") (pintype "passive"))
      (node (ref "IC1") (pin "13") (pinfunction "VDD_13") (pintype "power_in"))
      (node (ref "VDD_UC") (pin "1") (pinfunction "1_1") (pintype "passive"))
    )
    (net (code "38") (name "Net-(C10-Pad2)") (class "Default")
      (node (ref "C10") (pin "2") (pinfunction "2_2") (pintype "passive"))
      (node (ref "J1") (pin "2") (pinfunction "2_2") (pintype "bidirectional"))
      (node (ref "R11") (pin "2") (pinfunction "2_2") (pintype "passive"))
    )
    (net (code "39") (name "Net-(C11-Pad2)") (class "Default")
      (node (ref "C11") (pin "2") (pinfunction "2_2") (pintype "passive"))
      (node (ref "J1") (pin "3") (pinfunction "3_3") (pintype "bidirectional"))
      (node (ref "R12") (pin "2") (pinfunction "2_2") (pintype "passive"))
    )
    (net (code "40") (name "Net-(IC1-AN9{slash}PMCS1{slash}CN11{slash}RP15{slash}RB15)") (class "Default")
      (node (ref "IC1") (pin "26") (pinfunction "AN9/PMCS1/CN11/RP15/RB15_26") (pintype "bidirectional"))
      (node (ref "R9") (pin "2") (pinfunction "2_2") (pintype "passive"))
      (node (ref "SCLK/SCL") (pin "1") (pinfunction "1_1") (pintype "passive"))
    )
    (net (code "41") (name "Net-(IC1-AN10{slash}CVREF{slash}RTCC{slash}PMWR{slash}CN12{slash}RP14{slash}RB14)") (class "Default")
      (node (ref "IC1") (pin "25") (pinfunction "AN10/CVREF/RTCC/PMWR/CN12/RP14/RB14_25") (pintype "bidirectional"))
      (node (ref "R10") (pin "2") (pinfunction "2_2") (pintype "passive"))
      (node (ref "SDA/MOSI") (pin "1") (pinfunction "1_1") (pintype "passive"))
    )
    (net (code "42") (name "Net-(IC1-AN11{slash}PMRD{slash}CN13{slash}RP13{slash}RB13)") (class "Default")
      (node (ref "IC1") (pin "24") (pinfunction "AN11/PMRD/CN13/RP13/RB13_24") (pintype "bidirectional"))
      (node (ref "MISO") (pin "1") (pinfunction "1_1") (pintype "passive"))
    )
    (net (code "43") (name "Net-(IC1-AN12{slash}PMD0{slash}CN14{slash}RP12{slash}RB12)") (class "Default")
      (node (ref "CS") (pin "1") (pinfunction "1_1") (pintype "passive"))
      (node (ref "IC1") (pin "23") (pinfunction "AN12/PMD0/CN14/RP12/RB12_23") (pintype "bidirectional"))
    )
    (net (code "44") (name "Net-(IC1-INT0{slash}PMD5{slash}CN23{slash}RP7{slash}RB7)") (class "Default")
      (node (ref "CAT_ANGLE") (pin "1") (pinfunction "1_1") (pintype "passive"))
      (node (ref "IC1") (pin "16") (pinfunction "INT0/PMD5/CN23/RP7/RB7_16") (pintype "bidirectional"))
      (node (ref "R8") (pin "1") (pinfunction "1_1") (pintype "passive"))
    )
    (net (code "45") (name "Net-(IC1-PGEC1{slash}AN3{slash}C2IN+{slash}CN5{slash}RP1{slash}RB1)") (class "Default")
      (node (ref "IC1") (pin "5") (pinfunction "PGEC1/AN3/C2IN+/CN5/RP1/RB1_5") (pintype "bidirectional"))
      (node (ref "IC3") (pin "5") (pinfunction "D1_5") (pintype "bidirectional"))
      (node (ref "IC4") (pin "5") (pinfunction "D1_5") (pintype "bidirectional"))
      (node (ref "IC5") (pin "5") (pinfunction "D1_5") (pintype "bidirectional"))
      (node (ref "IC6") (pin "5") (pinfunction "D1_5") (pintype "bidirectional"))
      (node (ref "IC7") (pin "5") (pinfunction "D1_5") (pintype "bidirectional"))
      (node (ref "IC8") (pin "5") (pinfunction "D1_5") (pintype "bidirectional"))
    )
    (net (code "46") (name "Net-(IC1-PGEC2{slash}TMS{slash}PMD1{slash}CN15{slash}RP11{slash}RB11)") (class "Default")
      (node (ref "IC1") (pin "22") (pinfunction "PGEC2/TMS/PMD1/CN15/RP11/RB11_22") (pintype "bidirectional"))
      (node (ref "PGEC/GP") (pin "1") (pinfunction "1_1") (pintype "passive"))
    )
    (net (code "47") (name "Net-(IC1-PGEC3{slash}ASCL1{slash}PMD6{slash}CN24{slash}RP6{slash}RB6)") (class "Default")
      (node (ref "IC1") (pin "15") (pinfunction "PGEC3/ASCL1/PMD6/CN24/RP6/RB6_15") (pintype "bidirectional"))
      (node (ref "U1") (pin "3") (pinfunction "A2_3") (pintype "input"))
    )
    (net (code "48") (name "Net-(IC1-PGED1{slash}AN2{slash}C2IN-{slash}CN4{slash}RP0{slash}RB0)") (class "Default")
      (node (ref "IC1") (pin "4") (pinfunction "PGED1/AN2/C2IN-/CN4/RP0/RB0_4") (pintype "bidirectional"))
      (node (ref "IC3") (pin "4") (pinfunction "D0_4") (pintype "bidirectional"))
      (node (ref "IC4") (pin "4") (pinfunction "D0_4") (pintype "bidirectional"))
      (node (ref "IC5") (pin "4") (pinfunction "D0_4") (pintype "bidirectional"))
      (node (ref "IC6") (pin "4") (pinfunction "D0_4") (pintype "bidirectional"))
      (node (ref "IC7") (pin "4") (pinfunction "D0_4") (pintype "bidirectional"))
      (node (ref "IC8") (pin "4") (pinfunction "D0_4") (pintype "bidirectional"))
    )
    (net (code "49") (name "Net-(IC1-PGED2{slash}TDI{slash}PMD2{slash}CN16{slash}RP10{slash}RB10)") (class "Default")
      (node (ref "IC1") (pin "21") (pinfunction "PGED2/TDI/PMD2/CN16/RP10/RB10_21") (pintype "bidirectional"))
      (node (ref "PGED") (pin "1") (pinfunction "1_1") (pintype "passive"))
    )
    (net (code "50") (name "Net-(IC1-PGED3{slash}ASDA1{slash}PMD7{slash}CN27{slash}RP5{slash}RB5)") (class "Default")
      (node (ref "IC1") (pin "14") (pinfunction "PGED3/ASDA1/PMD7/CN27/RP5/RB5_14") (pintype "bidirectional"))
      (node (ref "U1") (pin "2") (pinfunction "A1_2") (pintype "input"))
    )
    (net (code "51") (name "Net-(IC1-RA0{slash}CN2{slash}VR+{slash}AN0)") (class "Default")
      (node (ref "CAT_ROTATION") (pin "1") (pinfunction "1_1") (pintype "passive"))
      (node (ref "IC1") (pin "2") (pinfunction "RA0/CN2/VR+/AN0_2") (pintype "bidirectional"))
      (node (ref "R7") (pin "2") (pinfunction "2_2") (pintype "passive"))
    )
    (net (code "52") (name "Net-(IC1-RA1{slash}CN3{slash}VR-{slash}AN1)") (class "Default")
      (node (ref "GP_LASER2") (pin "1") (pinfunction "1_1") (pintype "passive"))
      (node (ref "IC1") (pin "3") (pinfunction "RA1/CN3/VR-/AN1_3") (pintype "bidirectional"))
      (node (ref "R6") (pin "2") (pinfunction "2_2") (pintype "passive"))
    )
    (net (code "53") (name "Net-(IC1-RA2{slash}CN30{slash}CKLI{slash}OSCI)") (class "Default")
      (node (ref "C6") (pin "2") (pinfunction "2_2") (pintype "passive"))
      (node (ref "IC1") (pin "9") (pinfunction "RA2/CN30/CKLI/OSCI_9") (pintype "bidirectional"))
      (node (ref "Q1") (pin "1") (pinfunction "1_1") (pintype "passive"))
    )
    (net (code "54") (name "Net-(IC1-RA3{slash}CN29{slash}PMA0{slash}CLKO{slash}OSCO)") (class "Default")
      (node (ref "C8") (pin "2") (pinfunction "2_2") (pintype "passive"))
      (node (ref "IC1") (pin "10") (pinfunction "RA3/CN29/PMA0/CLKO/OSCO_10") (pintype "bidirectional"))
      (node (ref "Q1") (pin "2") (pinfunction "2_2") (pintype "passive"))
    )
    (net (code "55") (name "Net-(IC1-RA4{slash}CN0{slash}PMA1{slash}T1CK{slash}SOSCO)") (class "Default")
      (node (ref "GP_LASER1") (pin "1") (pinfunction "1_1") (pintype "passive"))
      (node (ref "IC1") (pin "12") (pinfunction "RA4/CN0/PMA1/T1CK/SOSCO_12") (pintype "bidirectional"))
      (node (ref "R5") (pin "2") (pinfunction "2_2") (pintype "passive"))
    )
    (net (code "56") (name "Net-(IC1-SCL2{slash}AN5{slash}C1IN+{slash}CN7{slash}RP3{slash}RB3)") (class "Default")
      (node (ref "IC1") (pin "7") (pinfunction "SCL2/AN5/C1IN+/CN7/RP3/RB3_7") (pintype "bidirectional"))
      (node (ref "IC3") (pin "13") (pinfunction "D3_13") (pintype "bidirectional"))
      (node (ref "IC4") (pin "13") (pinfunction "D3_13") (pintype "bidirectional"))
      (node (ref "IC5") (pin "13") (pinfunction "D3_13") (pintype "bidirectional"))
      (node (ref "IC6") (pin "13") (pinfunction "D3_13") (pintype "bidirectional"))
      (node (ref "IC7") (pin "13") (pinfunction "D3_13") (pintype "bidirectional"))
      (node (ref "IC8") (pin "13") (pinfunction "D3_13") (pintype "bidirectional"))
    )
    (net (code "57") (name "Net-(IC1-SDA2{slash}AN4{slash}C1IN-{slash}CN6{slash}RP2{slash}RB2)") (class "Default")
      (node (ref "IC1") (pin "6") (pinfunction "SDA2/AN4/C1IN-/CN6/RP2/RB2_6") (pintype "bidirectional"))
      (node (ref "IC3") (pin "12") (pinfunction "D2_12") (pintype "bidirectional"))
      (node (ref "IC4") (pin "12") (pinfunction "D2_12") (pintype "bidirectional"))
      (node (ref "IC5") (pin "12") (pinfunction "D2_12") (pintype "bidirectional"))
      (node (ref "IC6") (pin "12") (pinfunction "D2_12") (pintype "bidirectional"))
      (node (ref "IC7") (pin "12") (pinfunction "D2_12") (pintype "bidirectional"))
      (node (ref "IC8") (pin "12") (pinfunction "D2_12") (pintype "bidirectional"))
    )
    (net (code "58") (name "Net-(IC1-SOSCI{slash}PMBE{slash}CN1{slash}RP4{slash}RB4)") (class "Default")
      (node (ref "IC1") (pin "11") (pinfunction "SOSCI/PMBE/CN1/RP4/RB4_11") (pintype "bidirectional"))
      (node (ref "U1") (pin "1") (pinfunction "A0_1") (pintype "input"))
    )
    (net (code "59") (name "Net-(IC1-TCK{slash}SCL1{slash}PMD4{slash}CN22{slash}RP8{slash}RB8)") (class "Default")
      (node (ref "IC1") (pin "17") (pinfunction "TCK/SCL1/PMD4/CN22/RP8/RB8_17") (pintype "bidirectional"))
      (node (ref "IC13") (pin "1") (pinfunction "TXD_1") (pintype "bidirectional"))
    )
    (net (code "60") (name "Net-(IC1-TDO{slash}SDA1{slash}PMD3{slash}CN21{slash}RP9{slash}RB9)") (class "Default")
      (node (ref "IC1") (pin "18") (pinfunction "TDO/SDA1/PMD3/CN21/RP9/RB9_18") (pintype "bidirectional"))
      (node (ref "IC13") (pin "4") (pinfunction "RXD_4") (pintype "bidirectional"))
    )
    (net (code "61") (name "Net-(IC1-VCAP{slash}VDDCORE)") (class "Default")
      (node (ref "C7") (pin "2") (pinfunction "2_2") (pintype "passive"))
      (node (ref "IC1") (pin "20") (pinfunction "VCAP/VDDCORE_20") (pintype "power_in"))
    )
    (net (code "62") (name "Net-(IC1-~{MCLR})") (class "Default")
      (node (ref "IC1") (pin "1") (pinfunction "~{MCLR}_1") (pintype "input"))
      (node (ref "MCLR") (pin "1") (pinfunction "1_1") (pintype "passive"))
      (node (ref "R2") (pin "2") (pinfunction "2_2") (pintype "passive"))
    )
    (net (code "63") (name "Net-(IC2-ADJ)") (class "Default")
      (node (ref "IC2") (pin "1") (pinfunction "ADJ_1") (pintype "input"))
      (node (ref "R3") (pin "1") (pinfunction "1_1") (pintype "passive"))
      (node (ref "R4") (pin "2") (pinfunction "2_2") (pintype "passive"))
    )
    (net (code "64") (name "Net-(IC9-OUT1)") (class "Default")
      (node (ref "IC9") (pin "16") (pinfunction "OUT1_16") (pintype "bidirectional"))
      (node (ref "SM11") (pin "1") (pinfunction "1_1") (pintype "passive"))
    )
    (net (code "65") (name "Net-(IC9-OUT2)") (class "Default")
      (node (ref "IC9") (pin "15") (pinfunction "OUT2_15") (pintype "bidirectional"))
      (node (ref "SM12") (pin "1") (pinfunction "1_1") (pintype "passive"))
    )
    (net (code "66") (name "Net-(IC9-OUT3)") (class "Default")
      (node (ref "IC9") (pin "14") (pinfunction "OUT3_14") (pintype "bidirectional"))
      (node (ref "SM13") (pin "1") (pinfunction "1_1") (pintype "passive"))
    )
    (net (code "67") (name "Net-(IC9-OUT4)") (class "Default")
      (node (ref "IC9") (pin "13") (pinfunction "OUT4_13") (pintype "bidirectional"))
      (node (ref "SM14") (pin "1") (pinfunction "1_1") (pintype "passive"))
    )
    (net (code "68") (name "Net-(IC9-OUT5)") (class "Default")
      (node (ref "IC9") (pin "12") (pinfunction "OUT5_12") (pintype "bidirectional"))
      (node (ref "SM21") (pin "1") (pinfunction "1_1") (pintype "passive"))
    )
    (net (code "69") (name "Net-(IC9-OUT6)") (class "Default")
      (node (ref "IC9") (pin "11") (pinfunction "OUT6_11") (pintype "bidirectional"))
      (node (ref "SM22") (pin "1") (pinfunction "1_1") (pintype "passive"))
    )
    (net (code "70") (name "Net-(IC9-OUT7)") (class "Default")
      (node (ref "IC9") (pin "10") (pinfunction "OUT7_10") (pintype "bidirectional"))
      (node (ref "SM23") (pin "1") (pinfunction "1_1") (pintype "passive"))
    )
    (net (code "71") (name "Net-(IC10-OUT1)") (class "Default")
      (node (ref "IC10") (pin "16") (pinfunction "OUT1_16") (pintype "bidirectional"))
      (node (ref "SM24") (pin "1") (pinfunction "1_1") (pintype "passive"))
    )
    (net (code "72") (name "Net-(IC10-OUT2)") (class "Default")
      (node (ref "IC10") (pin "15") (pinfunction "OUT2_15") (pintype "bidirectional"))
      (node (ref "SM31") (pin "1") (pinfunction "1_1") (pintype "passive"))
    )
    (net (code "73") (name "Net-(IC10-OUT3)") (class "Default")
      (node (ref "IC10") (pin "14") (pinfunction "OUT3_14") (pintype "bidirectional"))
      (node (ref "SM32") (pin "1") (pinfunction "1_1") (pintype "passive"))
    )
    (net (code "74") (name "Net-(IC10-OUT4)") (class "Default")
      (node (ref "IC10") (pin "13") (pinfunction "OUT4_13") (pintype "bidirectional"))
      (node (ref "SM33") (pin "1") (pinfunction "1_1") (pintype "passive"))
    )
    (net (code "75") (name "Net-(IC10-OUT5)") (class "Default")
      (node (ref "IC10") (pin "12") (pinfunction "OUT5_12") (pintype "bidirectional"))
      (node (ref "SM34") (pin "1") (pinfunction "1_1") (pintype "passive"))
    )
    (net (code "76") (name "Net-(IC10-OUT6)") (class "Default")
      (node (ref "IC10") (pin "11") (pinfunction "OUT6_11") (pintype "bidirectional"))
      (node (ref "SM41") (pin "1") (pinfunction "1_1") (pintype "passive"))
    )
    (net (code "77") (name "Net-(IC10-OUT7)") (class "Default")
      (node (ref "IC10") (pin "10") (pinfunction "OUT7_10") (pintype "bidirectional"))
      (node (ref "SM42") (pin "1") (pinfunction "1_1") (pintype "passive"))
    )
    (net (code "78") (name "Net-(IC11-OUT1)") (class "Default")
      (node (ref "IC11") (pin "16") (pinfunction "OUT1_16") (pintype "bidirectional"))
      (node (ref "SM43") (pin "1") (pinfunction "1_1") (pintype "passive"))
    )
    (net (code "79") (name "Net-(IC11-OUT2)") (class "Default")
      (node (ref "IC11") (pin "15") (pinfunction "OUT2_15") (pintype "bidirectional"))
      (node (ref "SM44") (pin "1") (pinfunction "1_1") (pintype "passive"))
    )
    (net (code "80") (name "Net-(IC11-OUT3)") (class "Default")
      (node (ref "IC11") (pin "14") (pinfunction "OUT3_14") (pintype "bidirectional"))
      (node (ref "SM51") (pin "1") (pinfunction "1_1") (pintype "passive"))
    )
    (net (code "81") (name "Net-(IC11-OUT4)") (class "Default")
      (node (ref "IC11") (pin "13") (pinfunction "OUT4_13") (pintype "bidirectional"))
      (node (ref "SM52") (pin "1") (pinfunction "1_1") (pintype "passive"))
    )
    (net (code "82") (name "Net-(IC11-OUT5)") (class "Default")
      (node (ref "IC11") (pin "12") (pinfunction "OUT5_12") (pintype "bidirectional"))
      (node (ref "SM53") (pin "1") (pinfunction "1_1") (pintype "passive"))
    )
    (net (code "83") (name "Net-(IC11-OUT6)") (class "Default")
      (node (ref "IC11") (pin "11") (pinfunction "OUT6_11") (pintype "bidirectional"))
      (node (ref "SM54") (pin "1") (pinfunction "1_1") (pintype "passive"))
    )
    (net (code "84") (name "Net-(IC11-OUT7)") (class "Default")
      (node (ref "IC11") (pin "10") (pinfunction "OUT7_10") (pintype "bidirectional"))
      (node (ref "SM61") (pin "1") (pinfunction "1_1") (pintype "passive"))
    )
    (net (code "85") (name "Net-(IC12-OUT1)") (class "Default")
      (node (ref "IC12") (pin "16") (pinfunction "OUT1_16") (pintype "bidirectional"))
      (node (ref "SM62") (pin "1") (pinfunction "1_1") (pintype "passive"))
    )
    (net (code "86") (name "Net-(IC12-OUT2)") (class "Default")
      (node (ref "IC12") (pin "15") (pinfunction "OUT2_15") (pintype "bidirectional"))
      (node (ref "SM63") (pin "1") (pinfunction "1_1") (pintype "passive"))
    )
    (net (code "87") (name "Net-(IC12-OUT3)") (class "Default")
      (node (ref "IC12") (pin "14") (pinfunction "OUT3_14") (pintype "bidirectional"))
      (node (ref "SM64") (pin "1") (pinfunction "1_1") (pintype "passive"))
    )
    (net (code "88") (name "Net-(IC13-3V3OUT)") (class "Default")
      (node (ref "C9") (pin "2") (pinfunction "2_2") (pintype "passive"))
      (node (ref "IC13") (pin "10") (pinfunction "3V3OUT_10") (pintype "bidirectional"))
      (node (ref "IC13") (pin "11") (pinfunction "RESET#_11") (pintype "bidirectional"))
      (node (ref "IC13") (pin "3") (pinfunction "VCCIO_3") (pintype "bidirectional"))
    )
    (net (code "89") (name "Net-(IC13-USBDM)") (class "Default")
      (node (ref "IC13") (pin "9") (pinfunction "USBDM_9") (pintype "bidirectional"))
      (node (ref "R11") (pin "1") (pinfunction "1_1") (pintype "passive"))
    )
    (net (code "90") (name "Net-(IC13-USBDP)") (class "Default")
      (node (ref "IC13") (pin "8") (pinfunction "USBDP_8") (pintype "bidirectional"))
      (node (ref "R12") (pin "1") (pinfunction "1_1") (pintype "passive"))
    )
    (net (code "91") (name "Net-(PGEC-Pad1)") (class "Default")
      (node (ref "PGEC") (pin "1") (pinfunction "1_1") (pintype "passive"))
      (node (ref "PGEC_PROG") (pin "1") (pinfunction "1_1") (pintype "passive"))
    )
    (net (code "92") (name "Net-(VDD_PROG-Pad1)") (class "Default")
      (node (ref "VDD_PROG") (pin "1") (pinfunction "1_1") (pintype "passive"))
      (node (ref "VDD_PROG1") (pin "1") (pinfunction "1_1") (pintype "passive"))
    )
    (net (code "93") (name "VDD") (class "Default")
      (node (ref "C5") (pin "2") (pinfunction "2_2") (pintype "passive"))
      (node (ref "IC10") (pin "9") (pinfunction "COMMON_FREE_WHEELING_DIODES_9") (pintype "bidirectional"))
      (node (ref "IC11") (pin "9") (pinfunction "COMMON_FREE_WHEELING_DIODES_9") (pintype "bidirectional"))
      (node (ref "IC12") (pin "9") (pinfunction "COMMON_FREE_WHEELING_DIODES_9") (pintype "bidirectional"))
      (node (ref "IC2") (pin "3") (pinfunction "VI_3") (pintype "input"))
      (node (ref "IC9") (pin "9") (pinfunction "COMMON_FREE_WHEELING_DIODES_9") (pintype "bidirectional"))
      (node (ref "VDD") (pin "1") (pinfunction "1_1") (pintype "passive"))
    )
    (net (code "94") (name "unconnected-(C13-Pad1)") (class "Default")
      (node (ref "C13") (pin "1") (pinfunction "1_1") (pintype "passive"))
    )
    (net (code "95") (name "unconnected-(C15-Pad1)") (class "Default")
      (node (ref "C15") (pin "1") (pinfunction "1_1") (pintype "passive"))
    )
    (net (code "96") (name "unconnected-(C16-Pad1)") (class "Default")
      (node (ref "C16") (pin "1") (pinfunction "1_1") (pintype "passive"))
    )
    (net (code "97") (name "unconnected-(C17-Pad1)") (class "Default")
      (node (ref "C17") (pin "1") (pinfunction "1_1") (pintype "passive"))
    )
    (net (code "98") (name "unconnected-(C18-Pad1)") (class "Default")
      (node (ref "C18") (pin "1") (pinfunction "1_1") (pintype "passive"))
    )
    (net (code "99") (name "unconnected-(C19-Pad1)") (class "Default")
      (node (ref "C19") (pin "1") (pinfunction "1_1") (pintype "passive"))
    )
    (net (code "100") (name "unconnected-(IC3-~{Q0}-Pad3)") (class "Default")
      (node (ref "IC3") (pin "3") (pinfunction "~{Q0}_3") (pintype "bidirectional"))
    )
    (net (code "101") (name "unconnected-(IC3-~{Q1}-Pad6)") (class "Default")
      (node (ref "IC3") (pin "6") (pinfunction "~{Q1}_6") (pintype "bidirectional"))
    )
    (net (code "102") (name "unconnected-(IC3-~{Q2}-Pad11)") (class "Default")
      (node (ref "IC3") (pin "11") (pinfunction "~{Q2}_11") (pintype "bidirectional"))
    )
    (net (code "103") (name "unconnected-(IC3-~{Q3}-Pad14)") (class "Default")
      (node (ref "IC3") (pin "14") (pinfunction "~{Q3}_14") (pintype "bidirectional"))
    )
    (net (code "104") (name "unconnected-(IC4-~{Q0}-Pad3)") (class "Default")
      (node (ref "IC4") (pin "3") (pinfunction "~{Q0}_3") (pintype "bidirectional"))
    )
    (net (code "105") (name "unconnected-(IC4-~{Q1}-Pad6)") (class "Default")
      (node (ref "IC4") (pin "6") (pinfunction "~{Q1}_6") (pintype "bidirectional"))
    )
    (net (code "106") (name "unconnected-(IC4-~{Q2}-Pad11)") (class "Default")
      (node (ref "IC4") (pin "11") (pinfunction "~{Q2}_11") (pintype "bidirectional"))
    )
    (net (code "107") (name "unconnected-(IC4-~{Q3}-Pad14)") (class "Default")
      (node (ref "IC4") (pin "14") (pinfunction "~{Q3}_14") (pintype "bidirectional"))
    )
    (net (code "108") (name "unconnected-(IC5-~{Q0}-Pad3)") (class "Default")
      (node (ref "IC5") (pin "3") (pinfunction "~{Q0}_3") (pintype "bidirectional"))
    )
    (net (code "109") (name "unconnected-(IC5-~{Q1}-Pad6)") (class "Default")
      (node (ref "IC5") (pin "6") (pinfunction "~{Q1}_6") (pintype "bidirectional"))
    )
    (net (code "110") (name "unconnected-(IC5-~{Q2}-Pad11)") (class "Default")
      (node (ref "IC5") (pin "11") (pinfunction "~{Q2}_11") (pintype "bidirectional"))
    )
    (net (code "111") (name "unconnected-(IC5-~{Q3}-Pad14)") (class "Default")
      (node (ref "IC5") (pin "14") (pinfunction "~{Q3}_14") (pintype "bidirectional"))
    )
    (net (code "112") (name "unconnected-(IC6-~{Q0}-Pad3)") (class "Default")
      (node (ref "IC6") (pin "3") (pinfunction "~{Q0}_3") (pintype "bidirectional"))
    )
    (net (code "113") (name "unconnected-(IC6-~{Q1}-Pad6)") (class "Default")
      (node (ref "IC6") (pin "6") (pinfunction "~{Q1}_6") (pintype "bidirectional"))
    )
    (net (code "114") (name "unconnected-(IC6-~{Q2}-Pad11)") (class "Default")
      (node (ref "IC6") (pin "11") (pinfunction "~{Q2}_11") (pintype "bidirectional"))
    )
    (net (code "115") (name "unconnected-(IC6-~{Q3}-Pad14)") (class "Default")
      (node (ref "IC6") (pin "14") (pinfunction "~{Q3}_14") (pintype "bidirectional"))
    )
    (net (code "116") (name "unconnected-(IC7-~{Q0}-Pad3)") (class "Default")
      (node (ref "IC7") (pin "3") (pinfunction "~{Q0}_3") (pintype "bidirectional"))
    )
    (net (code "117") (name "unconnected-(IC7-~{Q1}-Pad6)") (class "Default")
      (node (ref "IC7") (pin "6") (pinfunction "~{Q1}_6") (pintype "bidirectional"))
    )
    (net (code "118") (name "unconnected-(IC7-~{Q2}-Pad11)") (class "Default")
      (node (ref "IC7") (pin "11") (pinfunction "~{Q2}_11") (pintype "bidirectional"))
    )
    (net (code "119") (name "unconnected-(IC7-~{Q3}-Pad14)") (class "Default")
      (node (ref "IC7") (pin "14") (pinfunction "~{Q3}_14") (pintype "bidirectional"))
    )
    (net (code "120") (name "unconnected-(IC8-~{Q0}-Pad3)") (class "Default")
      (node (ref "IC8") (pin "3") (pinfunction "~{Q0}_3") (pintype "bidirectional"))
    )
    (net (code "121") (name "unconnected-(IC8-~{Q1}-Pad6)") (class "Default")
      (node (ref "IC8") (pin "6") (pinfunction "~{Q1}_6") (pintype "bidirectional"))
    )
    (net (code "122") (name "unconnected-(IC8-~{Q2}-Pad11)") (class "Default")
      (node (ref "IC8") (pin "11") (pinfunction "~{Q2}_11") (pintype "bidirectional"))
    )
    (net (code "123") (name "unconnected-(IC8-~{Q3}-Pad14)") (class "Default")
      (node (ref "IC8") (pin "14") (pinfunction "~{Q3}_14") (pintype "bidirectional"))
    )
    (net (code "124") (name "unconnected-(IC12-IN4-Pad4)") (class "Default")
      (node (ref "IC12") (pin "4") (pinfunction "IN4_4") (pintype "bidirectional"))
    )
    (net (code "125") (name "unconnected-(IC12-IN5-Pad5)") (class "Default")
      (node (ref "IC12") (pin "5") (pinfunction "IN5_5") (pintype "bidirectional"))
    )
    (net (code "126") (name "unconnected-(IC12-IN6-Pad6)") (class "Default")
      (node (ref "IC12") (pin "6") (pinfunction "IN6_6") (pintype "bidirectional"))
    )
    (net (code "127") (name "unconnected-(IC12-IN7-Pad7)") (class "Default")
      (node (ref "IC12") (pin "7") (pinfunction "IN7_7") (pintype "bidirectional"))
    )
    (net (code "128") (name "unconnected-(IC12-OUT4-Pad13)") (class "Default")
      (node (ref "IC12") (pin "13") (pinfunction "OUT4_13") (pintype "bidirectional"))
    )
    (net (code "129") (name "unconnected-(IC12-OUT5-Pad12)") (class "Default")
      (node (ref "IC12") (pin "12") (pinfunction "OUT5_12") (pintype "bidirectional"))
    )
    (net (code "130") (name "unconnected-(IC12-OUT6-Pad11)") (class "Default")
      (node (ref "IC12") (pin "11") (pinfunction "OUT6_11") (pintype "bidirectional"))
    )
    (net (code "131") (name "unconnected-(IC12-OUT7-Pad10)") (class "Default")
      (node (ref "IC12") (pin "10") (pinfunction "OUT7_10") (pintype "bidirectional"))
    )
    (net (code "132") (name "unconnected-(IC13-CBUS0-Pad15)") (class "Default")
      (node (ref "IC13") (pin "15") (pinfunction "CBUS0_15") (pintype "bidirectional"))
    )
    (net (code "133") (name "unconnected-(IC13-CBUS1-Pad14)") (class "Default")
      (node (ref "IC13") (pin "14") (pinfunction "CBUS1_14") (pintype "bidirectional"))
    )
    (net (code "134") (name "unconnected-(IC13-CBUS2-Pad7)") (class "Default")
      (node (ref "IC13") (pin "7") (pinfunction "CBUS2_7") (pintype "bidirectional"))
    )
    (net (code "135") (name "unconnected-(IC13-CBUS3-Pad16)") (class "Default")
      (node (ref "IC13") (pin "16") (pinfunction "CBUS3_16") (pintype "bidirectional"))
    )
    (net (code "136") (name "unconnected-(IC13-CTS#-Pad6)") (class "Default")
      (node (ref "IC13") (pin "6") (pinfunction "CTS#_6") (pintype "bidirectional"))
    )
    (net (code "137") (name "unconnected-(IC13-RTS#-Pad2)") (class "Default")
      (node (ref "IC13") (pin "2") (pinfunction "RTS#_2") (pintype "bidirectional"))
    )
    (net (code "138") (name "unconnected-(J1-Pad1)") (class "Default")
      (node (ref "J1") (pin "1") (pinfunction "1_1") (pintype "bidirectional"))
    )
    (net (code "139") (name "unconnected-(J1-Pad4)") (class "Default")
      (node (ref "J1") (pin "4") (pinfunction "4_4") (pintype "bidirectional"))
    )
    (net (code "140") (name "unconnected-(U1-Y6-Pad9)") (class "Default")
      (node (ref "U1") (pin "9") (pinfunction "Y6_9") (pintype "output"))
    )
    (net (code "141") (name "unconnected-(U1-Y7-Pad7)") (class "Default")
      (node (ref "U1") (pin "7") (pinfunction "Y7_7") (pintype "output"))
    )
  )
)
